# NAVIGATION-PHERIPHERAL.net
KiCad netlist of a schematic drawn in Altium Designer
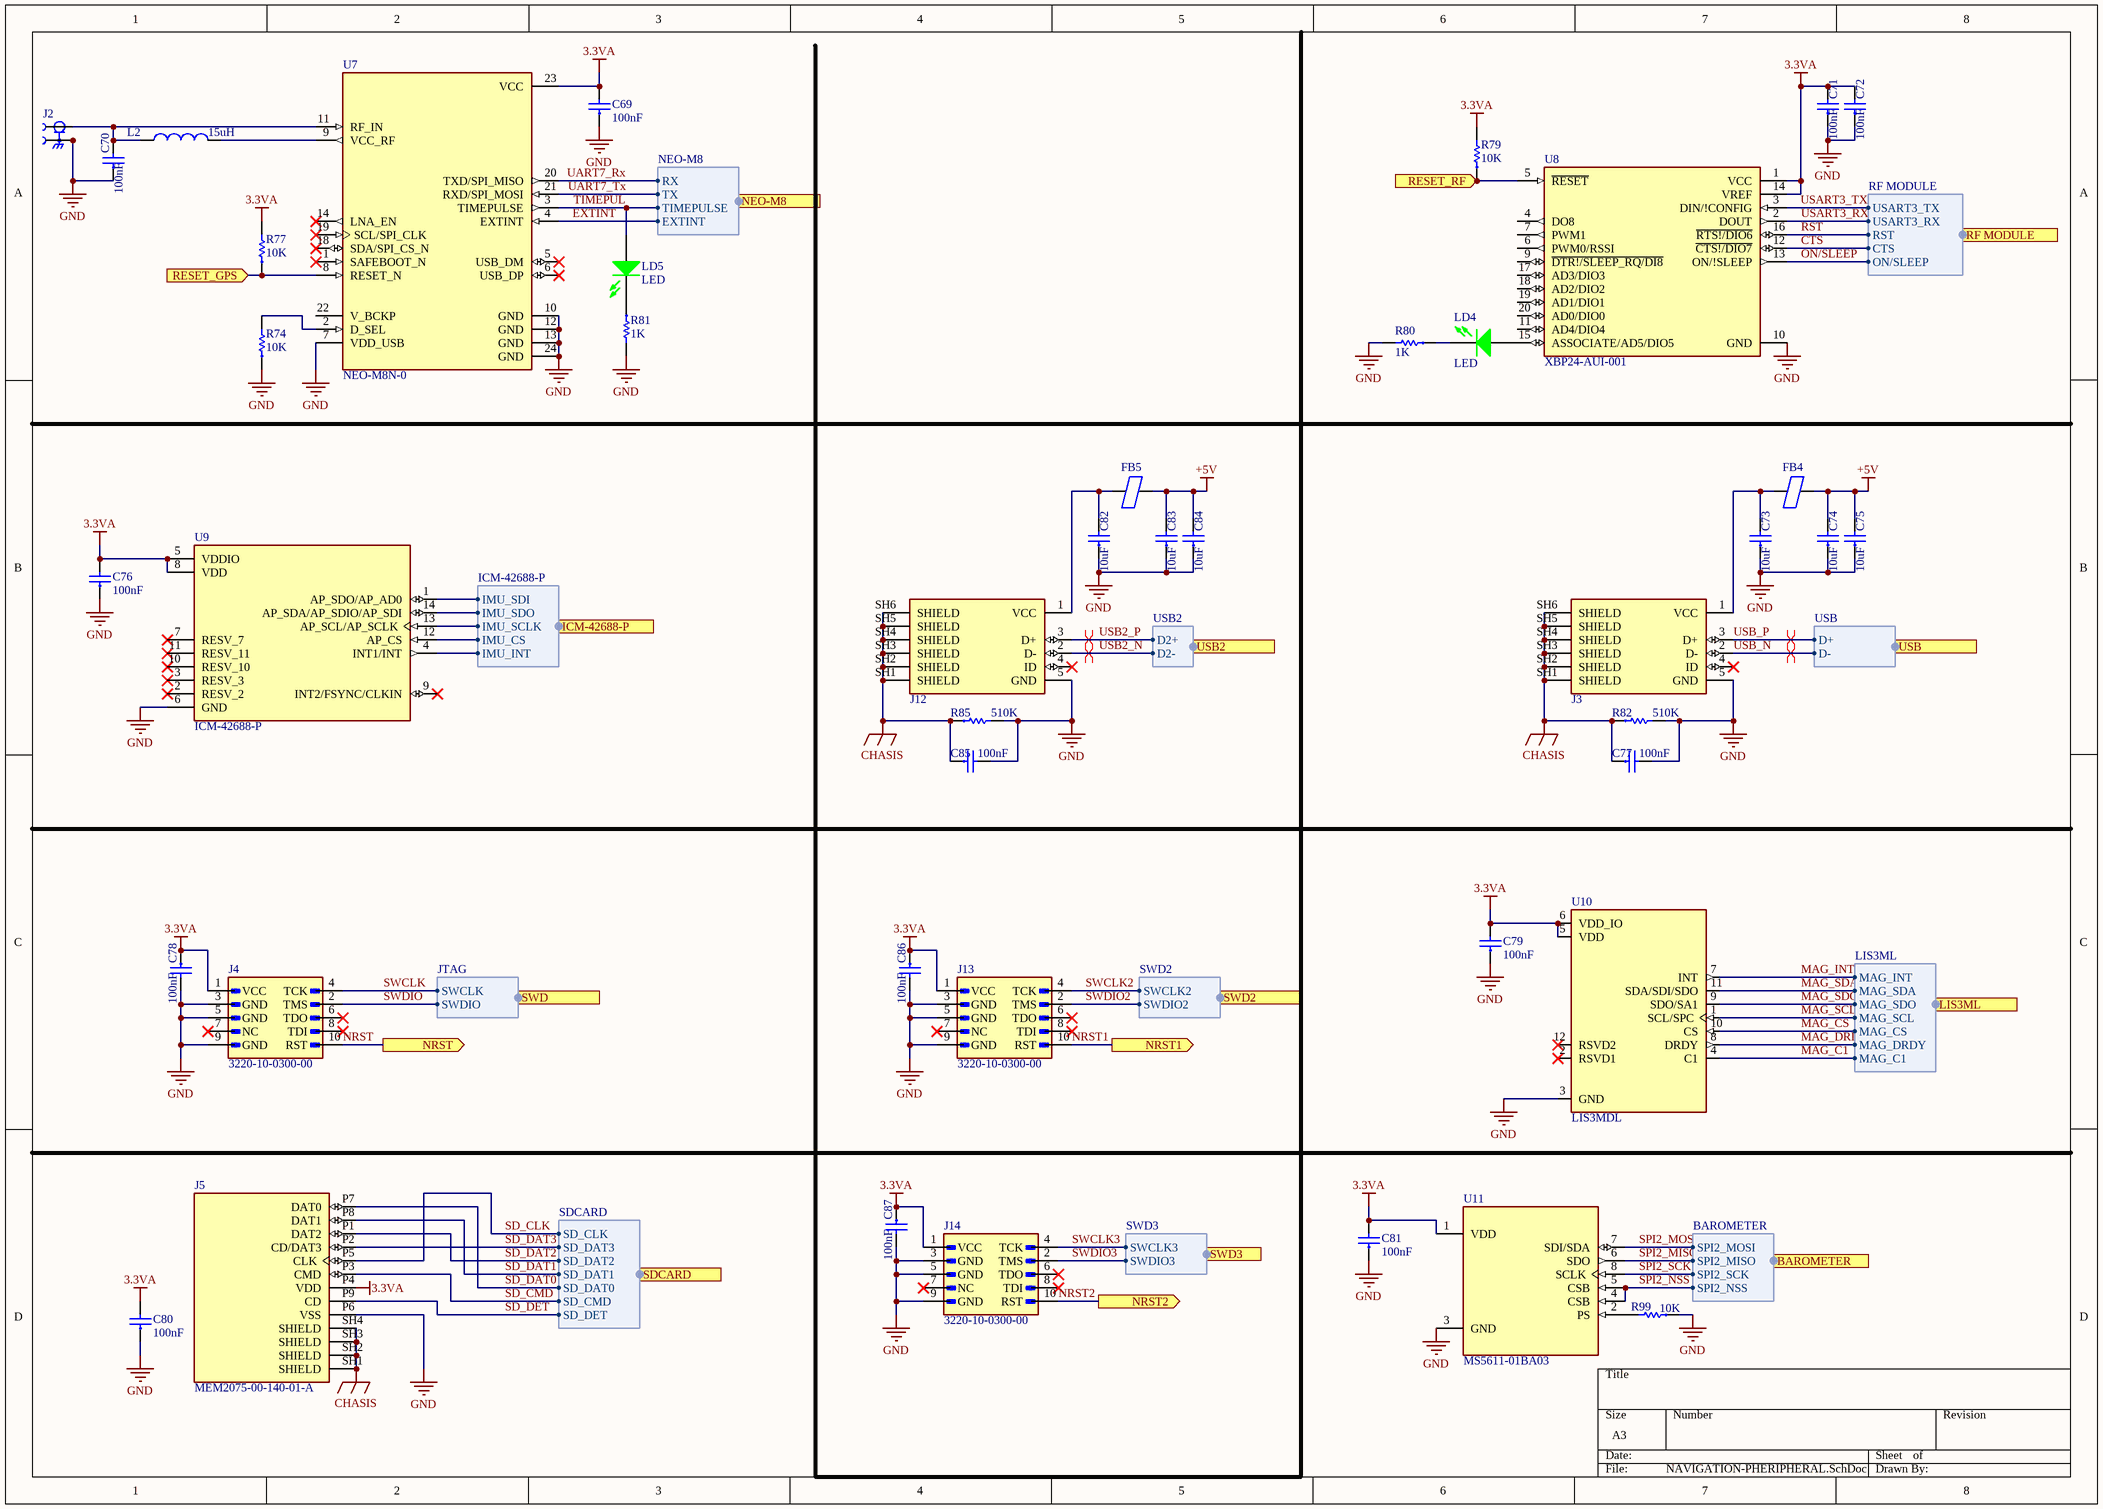
[diagram p0: NAVIGATION-PHERIPHERAL.SchDoc]

(export (version "E")
  (design (tool "Eeschema 10.0.6"))
  (components
    (comp (ref "C69")
      (value "100nF")
      (footprint "CAP-CER0402-0.5H")
      (description "CAP CER 100nF 10% 50V X7R 0402 SMD")
      (libsource (lib "2502-GMQLITE-MAIN") (part "CAPCER0013 100nF 10% 50V X7R 0402 SMD"))
    )
    (comp (ref "C70")
      (value "100nF")
      (footprint "CAP-CER0402-0.5H")
      (description "CAP CER 100nF 10% 50V X7R 0402 SMD")
      (libsource (lib "2502-GMQLITE-MAIN") (part "CAPCER0013 100nF 10% 50V X7R 0402 SMD"))
    )
    (comp (ref "C71")
      (value "100nF")
      (footprint "CAP-CER0402-0.5H")
      (description "CAP CER 100nF 10% 50V X7R 0402 SMD")
      (libsource (lib "2502-GMQLITE-MAIN") (part "CAPCER0013 100nF 10% 50V X7R 0402 SMD"))
    )
    (comp (ref "C72")
      (value "100nF")
      (footprint "CAP-CER0402-0.5H")
      (description "CAP CER 100nF 10% 50V X7R 0402 SMD")
      (libsource (lib "2502-GMQLITE-MAIN") (part "CAPCER0013 100nF 10% 50V X7R 0402 SMD"))
    )
    (comp (ref "C73")
      (value "10uF")
      (footprint "CAP-CER0402-20mil")
      (description "CAP CER 10uF 20% 6.3V X5R 0402 SMD")
      (libsource (lib "2502-GMQLITE-MAIN") (part "CAPCER0040 10uF 20% 6.3V X5R 0402 SMD"))
    )
    (comp (ref "C74")
      (value "10uF")
      (footprint "CAP-CER0402-20mil")
      (description "CAP CER 10uF 20% 6.3V X5R 0402 SMD")
      (libsource (lib "2502-GMQLITE-MAIN") (part "CAPCER0040 10uF 20% 6.3V X5R 0402 SMD"))
    )
    (comp (ref "C75")
      (value "10uF")
      (footprint "CAP-CER0402-20mil")
      (description "CAP CER 10uF 20% 6.3V X5R 0402 SMD")
      (libsource (lib "2502-GMQLITE-MAIN") (part "CAPCER0040 10uF 20% 6.3V X5R 0402 SMD"))
    )
    (comp (ref "C76")
      (value "100nF")
      (footprint "CAP-CER0402-0.5H")
      (description "CAP CER 100nF 10% 50V X7R 0402 SMD")
      (libsource (lib "2502-GMQLITE-MAIN") (part "CAPCER0013 100nF 10% 50V X7R 0402 SMD"))
    )
    (comp (ref "C77")
      (value "100nF")
      (footprint "CAP-CER0603-0.8H")
      (description "CAP CER 100nF 10% 50V X7R 0603 SMD")
      (libsource (lib "2502-GMQLITE-MAIN") (part "CAPCER0001 100nF 10% 50V X7R 0603 SMD"))
    )
    (comp (ref "C78")
      (value "100nF")
      (footprint "CAP-CER0402-0.5H")
      (description "CAP CER 100nF 10% 50V X7R 0402 SMD")
      (libsource (lib "2502-GMQLITE-MAIN") (part "CAPCER0013 100nF 10% 50V X7R 0402 SMD"))
    )
    (comp (ref "C79")
      (value "100nF")
      (footprint "CAP-CER0402-0.5H")
      (description "CAP CER 100nF 10% 50V X7R 0402 SMD")
      (libsource (lib "2502-GMQLITE-MAIN") (part "CAPCER0013 100nF 10% 50V X7R 0402 SMD"))
    )
    (comp (ref "C80")
      (value "100nF")
      (footprint "CAP-CER0402-0.5H")
      (description "CAP CER 100nF 10% 50V X7R 0402 SMD")
      (libsource (lib "2502-GMQLITE-MAIN") (part "CAPCER0013 100nF 10% 50V X7R 0402 SMD"))
    )
    (comp (ref "C81")
      (value "100nF")
      (footprint "CAP-CER0402-0.5H")
      (description "CAP CER 100nF 10% 50V X7R 0402 SMD")
      (libsource (lib "2502-GMQLITE-MAIN") (part "CAPCER0013 100nF 10% 50V X7R 0402 SMD"))
    )
    (comp (ref "C82")
      (value "10uF")
      (footprint "CAP-CER0402-20mil")
      (description "CAP CER 10uF 20% 6.3V X5R 0402 SMD")
      (libsource (lib "2502-GMQLITE-MAIN") (part "CAPCER0040 10uF 20% 6.3V X5R 0402 SMD"))
    )
    (comp (ref "C83")
      (value "10uF")
      (footprint "CAP-CER0402-20mil")
      (description "CAP CER 10uF 20% 6.3V X5R 0402 SMD")
      (libsource (lib "2502-GMQLITE-MAIN") (part "CAPCER0040 10uF 20% 6.3V X5R 0402 SMD"))
    )
    (comp (ref "C84")
      (value "10uF")
      (footprint "CAP-CER0402-20mil")
      (description "CAP CER 10uF 20% 6.3V X5R 0402 SMD")
      (libsource (lib "2502-GMQLITE-MAIN") (part "CAPCER0040 10uF 20% 6.3V X5R 0402 SMD"))
    )
    (comp (ref "C85")
      (value "100nF")
      (footprint "CAP-CER0603-0.8H")
      (description "CAP CER 100nF 10% 50V X7R 0603 SMD")
      (libsource (lib "2502-GMQLITE-MAIN") (part "CAPCER0001 100nF 10% 50V X7R 0603 SMD"))
    )
    (comp (ref "C86")
      (value "100nF")
      (footprint "CAP-CER0402-0.5H")
      (description "CAP CER 100nF 10% 50V X7R 0402 SMD")
      (libsource (lib "2502-GMQLITE-MAIN") (part "CAPCER0013 100nF 10% 50V X7R 0402 SMD"))
    )
    (comp (ref "C87")
      (value "100nF")
      (footprint "CAP-CER0402-0.5H")
      (description "CAP CER 100nF 10% 50V X7R 0402 SMD")
      (libsource (lib "2502-GMQLITE-MAIN") (part "CAPCER0013 100nF 10% 50V X7R 0402 SMD"))
    )
    (comp (ref "FB4")
      (value "100MHz 2A 50mOhm")
      (footprint "FB 0603")
      (description "Ferrite Beads Multi-Layer 120Ohm 25% 100MHz 2A 50mOhm DCR 0603 Paper T/R")
      (fields
        (field (name "MANUFACTURER") "Murata")
        (field (name "MANUFACTURER PART NUMBER") "BLM18PG121SN1D")
      )
      (libsource (lib "POWER_PIN_CAMERA") (part "BLM18PG121SN1D"))
    )
    (comp (ref "FB5")
      (value "100MHz 2A 50mOhm")
      (footprint "FB 0603")
      (description "Ferrite Beads Multi-Layer 120Ohm 25% 100MHz 2A 50mOhm DCR 0603 Paper T/R")
      (fields
        (field (name "MANUFACTURER") "Murata")
        (field (name "MANUFACTURER PART NUMBER") "BLM18PG121SN1D")
      )
      (libsource (lib "POWER_PIN_CAMERA") (part "BLM18PG121SN1D"))
    )
    (comp (ref "J2")
      (value "CONUFL001-SMD")
      (footprint "LINX_CONUFL001-SMD")
      (fields (field (name "MF") "Linx"))
      (libsource (lib "CONUFL001-SMD") (part "CONUFL001-SMD"))
    )
    (comp (ref "J3")
      (value "MICRO B")
      (footprint "MICRO USB B")
      (libsource (lib "BUCKCONVERTER") (part "MICRO USB B"))
    )
    (comp (ref "J4")
      (value "3220-10-0300-00")
      (footprint "CNC_3220-10-0300-00")
      (description "Connector Header Surface Mount 10 position 0.050 (1.27mm)")
      (fields (field (name "MF") "CNC Tech"))
      (libsource (lib "3220-10-0300-00") (part "3220-10-0300-00"))
    )
    (comp (ref "J5")
      (value "MEM2075-00-140-01-A")
      (footprint "GCT_MEM2075-00-140-01-A")
      (description "9 (8 + 1) Position Card Connector microSD Surface Mount, Right Angle Gold")
      (fields (field (name "MF") "Global Connector Technology"))
      (libsource (lib "PIKVM-PI4-0925") (part "MEM2075-00-140-01-A"))
    )
    (comp (ref "J12")
      (value "MICRO B")
      (footprint "MICRO USB B")
      (libsource (lib "BUCKCONVERTER") (part "MICRO USB B"))
    )
    (comp (ref "J13")
      (value "3220-10-0300-00")
      (footprint "CNC_3220-10-0300-00")
      (description "Connector Header Surface Mount 10 position 0.050 (1.27mm)")
      (fields (field (name "MF") "CNC Tech"))
      (libsource (lib "3220-10-0300-00") (part "3220-10-0300-00"))
    )
    (comp (ref "J14")
      (value "3220-10-0300-00")
      (footprint "CNC_3220-10-0300-00")
      (description "Connector Header Surface Mount 10 position 0.050 (1.27mm)")
      (fields (field (name "MF") "CNC Tech"))
      (libsource (lib "3220-10-0300-00") (part "3220-10-0300-00"))
    )
    (comp (ref "L2")
      (value "15uH")
      (footprint "INDC1106X70N")
      (fields
        (field (name "MF") "{'manufacturer': u'Murata Electronics'}")
        (field (name "MP") "LQW15DN100M00D")
      )
      (libsource (lib "LQW15DN100M00D") (part "LQW15DN100M00D"))
    )
    (comp (ref "LD4")
      (value "LED")
      (footprint "LED-IND0402-GRE-0.4H")
      (description "LED IND GRE CLR 2.4V 20mA 0402 SMD")
      (libsource (lib "2502-GMQLITE-MAIN") (part "LEDIND0005 GRE CLR 2.4V 20mA 0402 SMD"))
    )
    (comp (ref "LD5")
      (value "LED")
      (footprint "LED-IND0402-GRE-0.4H")
      (description "LED IND GRE CLR 2.4V 20mA 0402 SMD")
      (libsource (lib "2502-GMQLITE-MAIN") (part "LEDIND0005 GRE CLR 2.4V 20mA 0402 SMD"))
    )
    (comp (ref "R74")
      (value "10K")
      (footprint "RES-CHP0402-0.35H")
      (description "RES CHP 10K 1% 1/16W 0402 SMD")
      (libsource (lib "2502-GMQLITE-MAIN") (part "RESCHP0073 10K 1% 0402 SMD"))
    )
    (comp (ref "R77")
      (value "10K")
      (footprint "RES-CHP0402-0.35H")
      (description "RES CHP 10K 1% 1/16W 0402 SMD")
      (libsource (lib "2502-GMQLITE-MAIN") (part "RESCHP0073 10K 1% 0402 SMD"))
    )
    (comp (ref "R79")
      (value "10K")
      (footprint "RES-CHP0402-0.35H")
      (description "RES CHP 10K 1% 1/16W 0402 SMD")
      (libsource (lib "2502-GMQLITE-MAIN") (part "RESCHP0073 10K 1% 0402 SMD"))
    )
    (comp (ref "R80")
      (value "1K")
      (footprint "RES-CHP0402-0.35H")
      (description "RES CHP 100K 1% 1/16W 0402 SMD")
      (libsource (lib "2502-GMQLITE-MAIN") (part "RESCHP0097 100K 1% 0402 SMD"))
    )
    (comp (ref "R81")
      (value "1K")
      (footprint "RES-CHP0402-0.35H")
      (description "RES CHP 100K 1% 1/16W 0402 SMD")
      (libsource (lib "2502-GMQLITE-MAIN") (part "RESCHP0097 100K 1% 0402 SMD"))
    )
    (comp (ref "R82")
      (value "510K")
      (footprint "RES-CHP0402-0.35H")
      (description "RES CHP 510K 1% 1/16W 0402 SMD")
      (libsource (lib "2502-GMQLITE-MAIN") (part "RESCHP0114 510K 1% 0402 SMD"))
    )
    (comp (ref "R85")
      (value "510K")
      (footprint "RES-CHP0402-0.35H")
      (description "RES CHP 510K 1% 1/16W 0402 SMD")
      (libsource (lib "2502-GMQLITE-MAIN") (part "RESCHP0114 510K 1% 0402 SMD"))
    )
    (comp (ref "R99")
      (value "10K")
      (footprint "RES-CHP0402-0.35H")
      (description "RES CHP 100K 1% 1/16W 0402 SMD")
      (libsource (lib "2502-GMQLITE-MAIN") (part "RESCHP0097 100K 1% 0402 SMD"))
    )
    (comp (ref "U7")
      (value "NEO-M8N-0")
      (footprint "XCVR_NEO-M8N-0")
      (description "series RF Receiver BeiDou, Galileo, GLONASS, GNSS, GPS 1.575GHz -167dBm - - -")
      (fields (field (name "MF") "U-Blox America"))
      (libsource (lib "NEO-M8N-0") (part "NEO-M8N-0"))
    )
    (comp (ref "U8")
      (value "XBP24-AUI-001")
      (footprint "XBP24-AUI-001")
      (description "Xbee-Pro 802.15.4, 63mw, Wire Antenna, 250000 Bps; Higher Tran")
      (libsource (lib "XBP24-AUI-001") (part "XBP24-AUI-001"))
    )
    (comp (ref "U9")
      (value "ICM-42688-P")
      (footprint "PQFN50P300X250X97-14N")
      (description "Accelerometer, Gyroscope, 6 Axis Sensor Output")
      (libsource (lib "ICM-42688-P") (part "ICM-42688-P"))
    )
    (comp (ref "U10")
      (value "LIS3MDL")
      (footprint "XDCR_LIS3MDL")
      (description "Magnetoresistive Sensor X, Y, Z Axis 12-LGA (2x2)")
      (fields (field (name "MF") "STMicroelectronics"))
      (libsource (lib "LIS3MDL") (part "LIS3MDL"))
    )
    (comp (ref "U11")
      (value "MS5611-01BA03")
      (footprint "SON125P500X300X100-8N")
      (description "Pressure Sensor 0.15PSI ~ 17.4PSI (1kPa ~ 120kPa) Absolute - 24 b 8-SMD")
      (fields (field (name "MF") "TE Connectivity"))
      (libsource (lib "MS5611-01BA03") (part "MS5611-01BA03"))
    )
  )
  (nets
    (net (code "13") (name "+5V") (class "Default")
      (node (ref "C74") (pin "2") (pinfunction "2_2") (pintype "passive"))
      (node (ref "C75") (pin "2") (pinfunction "2_2") (pintype "passive"))
      (node (ref "C83") (pin "2") (pinfunction "2_2") (pintype "passive"))
      (node (ref "C84") (pin "2") (pinfunction "2_2") (pintype "passive"))
      (node (ref "FB4") (pin "2") (pinfunction "2_2") (pintype "passive"))
      (node (ref "FB5") (pin "2") (pinfunction "2_2") (pintype "passive"))
    )
    (net (code "14") (name "/CTS") (class "Default")
      (node (ref "U8") (pin "12") (pinfunction "~{CTS!/DIO7}_12") (pintype "bidirectional"))
    )
    (net (code "15") (name "/EXTINT") (class "Default")
      (node (ref "U7") (pin "4") (pinfunction "EXTINT_4") (pintype "input"))
    )
    (net (code "16") (name "/IMU_CS") (class "Default")
      (node (ref "U9") (pin "12") (pinfunction "AP_CS_12") (pintype "input"))
    )
    (net (code "17") (name "/IMU_INT") (class "Default")
      (node (ref "U9") (pin "4") (pinfunction "INT1/INT_4") (pintype "output"))
    )
    (net (code "18") (name "/IMU_SCLK") (class "Default")
      (node (ref "U9") (pin "13") (pinfunction "AP_SCL/AP_SCLK_13") (pintype "input"))
    )
    (net (code "19") (name "/IMU_SDI") (class "Default")
      (node (ref "U9") (pin "1") (pinfunction "AP_SDO/AP_AD0_1") (pintype "bidirectional"))
    )
    (net (code "20") (name "/IMU_SDO") (class "Default")
      (node (ref "U9") (pin "14") (pinfunction "AP_SDA/AP_SDIO/AP_SDI_14") (pintype "bidirectional"))
    )
    (net (code "21") (name "/MAG_C1") (class "Default")
      (node (ref "U10") (pin "4") (pinfunction "C1_4") (pintype "passive"))
    )
    (net (code "22") (name "/MAG_CS") (class "Default")
      (node (ref "U10") (pin "10") (pinfunction "CS_10") (pintype "input"))
    )
    (net (code "23") (name "/MAG_DRDY") (class "Default")
      (node (ref "U10") (pin "8") (pinfunction "DRDY_8") (pintype "output"))
    )
    (net (code "24") (name "/MAG_INT") (class "Default")
      (node (ref "U10") (pin "7") (pinfunction "INT_7") (pintype "output"))
    )
    (net (code "25") (name "/MAG_SCL") (class "Default")
      (node (ref "U10") (pin "1") (pinfunction "SCL/SPC_1") (pintype "input"))
    )
    (net (code "26") (name "/MAG_SDA") (class "Default")
      (node (ref "U10") (pin "11") (pinfunction "SDA/SDI/SDO_11") (pintype "bidirectional"))
    )
    (net (code "27") (name "/MAG_SDO") (class "Default")
      (node (ref "U10") (pin "9") (pinfunction "SDO/SA1_9") (pintype "bidirectional"))
    )
    (net (code "28") (name "/NRST") (class "Default")
      (node (ref "J4") (pin "10") (pinfunction "RST_10") (pintype "passive"))
    )
    (net (code "29") (name "/NRST1") (class "Default")
      (node (ref "J13") (pin "10") (pinfunction "RST_10") (pintype "passive"))
    )
    (net (code "30") (name "/NRST2") (class "Default")
      (node (ref "J14") (pin "10") (pinfunction "RST_10") (pintype "passive"))
    )
    (net (code "31") (name "/ON{slash}SLEEP") (class "Default")
      (node (ref "U8") (pin "13") (pinfunction "ON/!SLEEP_13") (pintype "output"))
    )
    (net (code "32") (name "/RESET_GPS") (class "Default")
      (node (ref "R77") (pin "1") (pinfunction "1_1") (pintype "passive"))
      (node (ref "U7") (pin "8") (pinfunction "RESET_N_8") (pintype "input"))
    )
    (net (code "33") (name "/RESET_RF") (class "Default")
      (node (ref "R79") (pin "1") (pinfunction "1_1") (pintype "passive"))
      (node (ref "U8") (pin "5") (pinfunction "~{RESET}_5") (pintype "input"))
    )
    (net (code "34") (name "/RST") (class "Default")
      (node (ref "U8") (pin "16") (pinfunction "~{RTS!/DIO6}_16") (pintype "bidirectional"))
    )
    (net (code "35") (name "/SD_CLK") (class "Default")
      (node (ref "J5") (pin "P5") (pinfunction "CLK_P5") (pintype "bidirectional"))
    )
    (net (code "36") (name "/SD_CMD") (class "Default")
      (node (ref "J5") (pin "P3") (pinfunction "CMD_P3") (pintype "bidirectional"))
    )
    (net (code "37") (name "/SD_DAT0") (class "Default")
      (node (ref "J5") (pin "P7") (pinfunction "DAT0_P7") (pintype "bidirectional"))
    )
    (net (code "38") (name "/SD_DAT1") (class "Default")
      (node (ref "J5") (pin "P8") (pinfunction "DAT1_P8") (pintype "bidirectional"))
    )
    (net (code "39") (name "/SD_DAT2") (class "Default")
      (node (ref "J5") (pin "P1") (pinfunction "DAT2_P1") (pintype "bidirectional"))
    )
    (net (code "40") (name "/SD_DAT3") (class "Default")
      (node (ref "J5") (pin "P2") (pinfunction "CD/DAT3_P2") (pintype "bidirectional"))
    )
    (net (code "41") (name "/SD_DET") (class "Default")
      (node (ref "J5") (pin "P9") (pinfunction "CD_P9") (pintype "passive"))
    )
    (net (code "42") (name "/SPI2_MISO") (class "Default")
      (node (ref "U11") (pin "6") (pinfunction "SDO_6") (pintype "output"))
    )
    (net (code "43") (name "/SPI2_MOSI") (class "Default")
      (node (ref "U11") (pin "7") (pinfunction "SDI/SDA_7") (pintype "bidirectional"))
    )
    (net (code "44") (name "/SPI2_NSS") (class "Default")
      (node (ref "U11") (pin "4") (pinfunction "CSB_4") (pintype "input"))
      (node (ref "U11") (pin "5") (pinfunction "CSB_5") (pintype "input"))
    )
    (net (code "45") (name "/SPI2_SCK") (class "Default")
      (node (ref "U11") (pin "8") (pinfunction "SCLK_8") (pintype "input"))
    )
    (net (code "46") (name "/SWCLK") (class "Default")
      (node (ref "J4") (pin "4") (pinfunction "TCK_4") (pintype "passive"))
    )
    (net (code "47") (name "/SWCLK2") (class "Default")
      (node (ref "J13") (pin "4") (pinfunction "TCK_4") (pintype "passive"))
    )
    (net (code "48") (name "/SWCLK3") (class "Default")
      (node (ref "J14") (pin "4") (pinfunction "TCK_4") (pintype "passive"))
    )
    (net (code "49") (name "/SWDIO") (class "Default")
      (node (ref "J4") (pin "2") (pinfunction "TMS_2") (pintype "passive"))
    )
    (net (code "50") (name "/SWDIO2") (class "Default")
      (node (ref "J13") (pin "2") (pinfunction "TMS_2") (pintype "passive"))
    )
    (net (code "51") (name "/SWDIO3") (class "Default")
      (node (ref "J14") (pin "2") (pinfunction "TMS_2") (pintype "passive"))
    )
    (net (code "52") (name "/TIMEPUL") (class "Default")
      (node (ref "LD5") (pin "1") (pinfunction "A_1") (pintype "passive"))
      (node (ref "U7") (pin "3") (pinfunction "TIMEPULSE_3") (pintype "output"))
    )
    (net (code "53") (name "/UART7_Rx") (class "Default")
      (node (ref "U7") (pin "20") (pinfunction "TXD/SPI_MISO_20") (pintype "output"))
    )
    (net (code "54") (name "/UART7_Tx") (class "Default")
      (node (ref "U7") (pin "21") (pinfunction "RXD/SPI_MOSI_21") (pintype "input"))
    )
    (net (code "55") (name "/USART3_RX") (class "Default")
      (node (ref "U8") (pin "2") (pinfunction "DOUT_2") (pintype "output"))
    )
    (net (code "56") (name "/USART3_TX") (class "Default")
      (node (ref "U8") (pin "3") (pinfunction "DIN/!CONFIG_3") (pintype "input"))
    )
    (net (code "57") (name "/USB2_N") (class "Default")
      (node (ref "J12") (pin "2") (pinfunction "D-_2") (pintype "bidirectional"))
    )
    (net (code "58") (name "/USB2_P") (class "Default")
      (node (ref "J12") (pin "3") (pinfunction "D+_3") (pintype "bidirectional"))
    )
    (net (code "59") (name "/USB_N") (class "Default")
      (node (ref "J3") (pin "2") (pinfunction "D-_2") (pintype "bidirectional"))
    )
    (net (code "60") (name "/USB_P") (class "Default")
      (node (ref "J3") (pin "3") (pinfunction "D+_3") (pintype "bidirectional"))
    )
    (net (code "72") (name "3.3VA") (class "Default")
      (node (ref "C69") (pin "2") (pinfunction "2_2") (pintype "passive"))
      (node (ref "C71") (pin "2") (pinfunction "2_2") (pintype "passive"))
      (node (ref "C72") (pin "2") (pinfunction "2_2") (pintype "passive"))
      (node (ref "C76") (pin "2") (pinfunction "2_2") (pintype "passive"))
      (node (ref "C78") (pin "1") (pinfunction "1_1") (pintype "passive"))
      (node (ref "C79") (pin "2") (pinfunction "2_2") (pintype "passive"))
      (node (ref "C80") (pin "2") (pinfunction "2_2") (pintype "passive"))
      (node (ref "C81") (pin "2") (pinfunction "2_2") (pintype "passive"))
      (node (ref "C86") (pin "1") (pinfunction "1_1") (pintype "passive"))
      (node (ref "C87") (pin "1") (pinfunction "1_1") (pintype "passive"))
      (node (ref "J13") (pin "1") (pinfunction "VCC_1") (pintype "passive"))
      (node (ref "J14") (pin "1") (pinfunction "VCC_1") (pintype "passive"))
      (node (ref "J4") (pin "1") (pinfunction "VCC_1") (pintype "passive"))
      (node (ref "J5") (pin "P4") (pinfunction "VDD_P4") (pintype "power_in"))
      (node (ref "R77") (pin "2") (pinfunction "2_2") (pintype "passive"))
      (node (ref "R79") (pin "2") (pinfunction "2_2") (pintype "passive"))
      (node (ref "U10") (pin "5") (pinfunction "VDD_5") (pintype "power_in"))
      (node (ref "U10") (pin "6") (pinfunction "VDD_IO_6") (pintype "power_in"))
      (node (ref "U11") (pin "1") (pinfunction "VDD_1") (pintype "power_in"))
      (node (ref "U7") (pin "23") (pinfunction "VCC_23") (pintype "power_in"))
      (node (ref "U8") (pin "1") (pinfunction "VCC_1") (pintype "power_in"))
      (node (ref "U8") (pin "14") (pinfunction "VREF_14") (pintype "power_in"))
      (node (ref "U9") (pin "5") (pinfunction "VDDIO_5") (pintype "power_in"))
      (node (ref "U9") (pin "8") (pinfunction "VDD_8") (pintype "power_in"))
    )
    (net (code "73") (name "CHASIS") (class "Default")
      (node (ref "C77") (pin "1") (pinfunction "1_1") (pintype "passive"))
      (node (ref "C85") (pin "1") (pinfunction "1_1") (pintype "passive"))
      (node (ref "J12") (pin "SH1") (pinfunction "SHIELD_SH1") (pintype "passive"))
      (node (ref "J12") (pin "SH2") (pinfunction "SHIELD_SH2") (pintype "passive"))
      (node (ref "J12") (pin "SH3") (pinfunction "SHIELD_SH3") (pintype "passive"))
      (node (ref "J12") (pin "SH4") (pinfunction "SHIELD_SH4") (pintype "passive"))
      (node (ref "J12") (pin "SH5") (pinfunction "SHIELD_SH5") (pintype "passive"))
      (node (ref "J12") (pin "SH6") (pinfunction "SHIELD_SH6") (pintype "passive"))
      (node (ref "J3") (pin "SH1") (pinfunction "SHIELD_SH1") (pintype "passive"))
      (node (ref "J3") (pin "SH2") (pinfunction "SHIELD_SH2") (pintype "passive"))
      (node (ref "J3") (pin "SH3") (pinfunction "SHIELD_SH3") (pintype "passive"))
      (node (ref "J3") (pin "SH4") (pinfunction "SHIELD_SH4") (pintype "passive"))
      (node (ref "J3") (pin "SH5") (pinfunction "SHIELD_SH5") (pintype "passive"))
      (node (ref "J3") (pin "SH6") (pinfunction "SHIELD_SH6") (pintype "passive"))
      (node (ref "J5") (pin "SH1") (pinfunction "SHIELD_SH1") (pintype "power_in"))
      (node (ref "J5") (pin "SH2") (pinfunction "SHIELD_SH2") (pintype "power_in"))
      (node (ref "J5") (pin "SH3") (pinfunction "SHIELD_SH3") (pintype "power_in"))
      (node (ref "J5") (pin "SH4") (pinfunction "SHIELD_SH4") (pintype "power_in"))
      (node (ref "R82") (pin "1") (pinfunction "1_1") (pintype "passive"))
      (node (ref "R85") (pin "1") (pinfunction "1_1") (pintype "passive"))
    )
    (net (code "74") (name "GND") (class "Default")
      (node (ref "C69") (pin "1") (pinfunction "1_1") (pintype "passive"))
      (node (ref "C70") (pin "1") (pinfunction "1_1") (pintype "passive"))
      (node (ref "C71") (pin "1") (pinfunction "1_1") (pintype "passive"))
      (node (ref "C72") (pin "1") (pinfunction "1_1") (pintype "passive"))
      (node (ref "C73") (pin "1") (pinfunction "1_1") (pintype "passive"))
      (node (ref "C74") (pin "1") (pinfunction "1_1") (pintype "passive"))
      (node (ref "C75") (pin "1") (pinfunction "1_1") (pintype "passive"))
      (node (ref "C76") (pin "1") (pinfunction "1_1") (pintype "passive"))
      (node (ref "C77") (pin "2") (pinfunction "2_2") (pintype "passive"))
      (node (ref "C78") (pin "2") (pinfunction "2_2") (pintype "passive"))
      (node (ref "C79") (pin "1") (pinfunction "1_1") (pintype "passive"))
      (node (ref "C80") (pin "1") (pinfunction "1_1") (pintype "passive"))
      (node (ref "C81") (pin "1") (pinfunction "1_1") (pintype "passive"))
      (node (ref "C82") (pin "1") (pinfunction "1_1") (pintype "passive"))
      (node (ref "C83") (pin "1") (pinfunction "1_1") (pintype "passive"))
      (node (ref "C84") (pin "1") (pinfunction "1_1") (pintype "passive"))
      (node (ref "C85") (pin "2") (pinfunction "2_2") (pintype "passive"))
      (node (ref "C86") (pin "2") (pinfunction "2_2") (pintype "passive"))
      (node (ref "C87") (pin "2") (pinfunction "2_2") (pintype "passive"))
      (node (ref "J12") (pin "5") (pinfunction "GND_5") (pintype "power_in"))
      (node (ref "J13") (pin "3") (pinfunction "GND_3") (pintype "passive"))
      (node (ref "J13") (pin "5") (pinfunction "GND_5") (pintype "passive"))
      (node (ref "J13") (pin "9") (pinfunction "GND_9") (pintype "passive"))
      (node (ref "J14") (pin "3") (pinfunction "GND_3") (pintype "passive"))
      (node (ref "J14") (pin "5") (pinfunction "GND_5") (pintype "passive"))
      (node (ref "J14") (pin "9") (pinfunction "GND_9") (pintype "passive"))
      (node (ref "J2") (pin "2") (pinfunction "2_2") (pintype "passive"))
      (node (ref "J2") (pin "3") (pinfunction "2_3") (pintype "passive"))
      (node (ref "J3") (pin "5") (pinfunction "GND_5") (pintype "power_in"))
      (node (ref "J4") (pin "3") (pinfunction "GND_3") (pintype "passive"))
      (node (ref "J4") (pin "5") (pinfunction "GND_5") (pintype "passive"))
      (node (ref "J4") (pin "9") (pinfunction "GND_9") (pintype "passive"))
      (node (ref "J5") (pin "P6") (pinfunction "VSS_P6") (pintype "power_in"))
      (node (ref "R74") (pin "1") (pinfunction "1_1") (pintype "passive"))
      (node (ref "R80") (pin "2") (pinfunction "2_2") (pintype "passive"))
      (node (ref "R81") (pin "2") (pinfunction "2_2") (pintype "passive"))
      (node (ref "R82") (pin "2") (pinfunction "2_2") (pintype "passive"))
      (node (ref "R85") (pin "2") (pinfunction "2_2") (pintype "passive"))
      (node (ref "R99") (pin "1") (pinfunction "1_1") (pintype "passive"))
      (node (ref "U10") (pin "3") (pinfunction "GND_3") (pintype "power_in"))
      (node (ref "U11") (pin "3") (pinfunction "GND_3") (pintype "power_in"))
      (node (ref "U7") (pin "10") (pinfunction "GND_10") (pintype "power_in"))
      (node (ref "U7") (pin "12") (pinfunction "GND_12") (pintype "power_in"))
      (node (ref "U7") (pin "13") (pinfunction "GND_13") (pintype "power_in"))
      (node (ref "U7") (pin "24") (pinfunction "GND_24") (pintype "power_in"))
      (node (ref "U7") (pin "7") (pinfunction "VDD_USB_7") (pintype "power_in"))
      (node (ref "U8") (pin "10") (pinfunction "GND_10") (pintype "power_in"))
      (node (ref "U9") (pin "6") (pinfunction "GND_6") (pintype "power_in"))
    )
    (net (code "75") (name "Net-(J3-VCC)") (class "Default")
      (node (ref "C73") (pin "2") (pinfunction "2_2") (pintype "passive"))
      (node (ref "FB4") (pin "1") (pinfunction "1_1") (pintype "passive"))
      (node (ref "J3") (pin "1") (pinfunction "VCC_1") (pintype "power_in"))
    )
    (net (code "76") (name "Net-(J12-VCC)") (class "Default")
      (node (ref "C82") (pin "2") (pinfunction "2_2") (pintype "passive"))
      (node (ref "FB5") (pin "1") (pinfunction "1_1") (pintype "passive"))
      (node (ref "J12") (pin "1") (pinfunction "VCC_1") (pintype "power_in"))
    )
    (net (code "77") (name "Net-(LD4-A)") (class "Default")
      (node (ref "LD4") (pin "1") (pinfunction "A_1") (pintype "passive"))
      (node (ref "U8") (pin "15") (pinfunction "ASSOCIATE/AD5/DIO5_15") (pintype "bidirectional"))
    )
    (net (code "78") (name "Net-(LD4-K)") (class "Default")
      (node (ref "LD4") (pin "2") (pinfunction "K_2") (pintype "passive"))
      (node (ref "R80") (pin "1") (pinfunction "1_1") (pintype "passive"))
    )
    (net (code "79") (name "Net-(LD5-K)") (class "Default")
      (node (ref "LD5") (pin "2") (pinfunction "K_2") (pintype "passive"))
      (node (ref "R81") (pin "1") (pinfunction "1_1") (pintype "passive"))
    )
    (net (code "80") (name "Net-(U7-D_SEL)") (class "Default")
      (node (ref "R74") (pin "2") (pinfunction "2_2") (pintype "passive"))
      (node (ref "U7") (pin "2") (pinfunction "D_SEL_2") (pintype "input"))
    )
    (net (code "81") (name "Net-(U7-RF_IN)") (class "Default")
      (node (ref "C70") (pin "2") (pinfunction "2_2") (pintype "passive"))
      (node (ref "J2") (pin "1") (pinfunction "1_1") (pintype "passive"))
      (node (ref "L2") (pin "1") (pinfunction "1_1") (pintype "passive"))
      (node (ref "U7") (pin "11") (pinfunction "RF_IN_11") (pintype "input"))
    )
    (net (code "82") (name "Net-(U7-VCC_RF)") (class "Default")
      (node (ref "L2") (pin "2") (pinfunction "2_2") (pintype "passive"))
      (node (ref "U7") (pin "9") (pinfunction "VCC_RF_9") (pintype "output"))
    )
    (net (code "83") (name "Net-(U11-PS)") (class "Default")
      (node (ref "R99") (pin "2") (pinfunction "2_2") (pintype "passive"))
      (node (ref "U11") (pin "2") (pinfunction "PS_2") (pintype "input"))
    )
    (net (code "84") (name "unconnected-(J3-ID-Pad4)") (class "Default")
      (node (ref "J3") (pin "4") (pinfunction "ID_4") (pintype "bidirectional+no_connect"))
    )
    (net (code "85") (name "unconnected-(J4-NC-Pad7)") (class "Default")
      (node (ref "J4") (pin "7") (pinfunction "NC_7") (pintype "passive+no_connect"))
    )
    (net (code "86") (name "unconnected-(J4-TDI-Pad8)") (class "Default")
      (node (ref "J4") (pin "8") (pinfunction "TDI_8") (pintype "passive+no_connect"))
    )
    (net (code "87") (name "unconnected-(J4-TDO-Pad6)") (class "Default")
      (node (ref "J4") (pin "6") (pinfunction "TDO_6") (pintype "passive+no_connect"))
    )
    (net (code "88") (name "unconnected-(J12-ID-Pad4)") (class "Default")
      (node (ref "J12") (pin "4") (pinfunction "ID_4") (pintype "bidirectional+no_connect"))
    )
    (net (code "89") (name "unconnected-(J13-NC-Pad7)") (class "Default")
      (node (ref "J13") (pin "7") (pinfunction "NC_7") (pintype "passive+no_connect"))
    )
    (net (code "90") (name "unconnected-(J13-TDI-Pad8)") (class "Default")
      (node (ref "J13") (pin "8") (pinfunction "TDI_8") (pintype "passive+no_connect"))
    )
    (net (code "91") (name "unconnected-(J13-TDO-Pad6)") (class "Default")
      (node (ref "J13") (pin "6") (pinfunction "TDO_6") (pintype "passive+no_connect"))
    )
    (net (code "92") (name "unconnected-(J14-NC-Pad7)") (class "Default")
      (node (ref "J14") (pin "7") (pinfunction "NC_7") (pintype "passive+no_connect"))
    )
    (net (code "93") (name "unconnected-(J14-TDI-Pad8)") (class "Default")
      (node (ref "J14") (pin "8") (pinfunction "TDI_8") (pintype "passive+no_connect"))
    )
    (net (code "94") (name "unconnected-(J14-TDO-Pad6)") (class "Default")
      (node (ref "J14") (pin "6") (pinfunction "TDO_6") (pintype "passive+no_connect"))
    )
    (net (code "95") (name "unconnected-(U7-LNA_EN-Pad14)") (class "Default")
      (node (ref "U7") (pin "14") (pinfunction "LNA_EN_14") (pintype "output+no_connect"))
    )
    (net (code "96") (name "unconnected-(U7-SAFEBOOT_N-Pad1)") (class "Default")
      (node (ref "U7") (pin "1") (pinfunction "SAFEBOOT_N_1") (pintype "input+no_connect"))
    )
    (net (code "97") (name "unconnected-(U7-SCL{slash}SPI_CLK-Pad19)") (class "Default")
      (node (ref "U7") (pin "19") (pinfunction "SCL/SPI_CLK_19") (pintype "input+no_connect"))
    )
    (net (code "98") (name "unconnected-(U7-SDA{slash}SPI_CS_N-Pad18)") (class "Default")
      (node (ref "U7") (pin "18") (pinfunction "SDA/SPI_CS_N_18") (pintype "bidirectional+no_connect"))
    )
    (net (code "99") (name "unconnected-(U7-USB_DM-Pad5)") (class "Default")
      (node (ref "U7") (pin "5") (pinfunction "USB_DM_5") (pintype "bidirectional+no_connect"))
    )
    (net (code "100") (name "unconnected-(U7-USB_DP-Pad6)") (class "Default")
      (node (ref "U7") (pin "6") (pinfunction "USB_DP_6") (pintype "bidirectional+no_connect"))
    )
    (net (code "101") (name "unconnected-(U7-V_BCKP-Pad22)") (class "Default")
      (node (ref "U7") (pin "22") (pinfunction "V_BCKP_22") (pintype "power_in"))
    )
    (net (code "102") (name "unconnected-(U8-AD0{slash}DIO0-Pad20)") (class "Default")
      (node (ref "U8") (pin "20") (pinfunction "AD0/DIO0_20") (pintype "bidirectional"))
    )
    (net (code "103") (name "unconnected-(U8-AD1{slash}DIO1-Pad19)") (class "Default")
      (node (ref "U8") (pin "19") (pinfunction "AD1/DIO1_19") (pintype "bidirectional"))
    )
    (net (code "104") (name "unconnected-(U8-AD2{slash}DIO2-Pad18)") (class "Default")
      (node (ref "U8") (pin "18") (pinfunction "AD2/DIO2_18") (pintype "bidirectional"))
    )
    (net (code "105") (name "unconnected-(U8-AD3{slash}DIO3-Pad17)") (class "Default")
      (node (ref "U8") (pin "17") (pinfunction "AD3/DIO3_17") (pintype "bidirectional"))
    )
    (net (code "106") (name "unconnected-(U8-AD4{slash}DIO4-Pad11)") (class "Default")
      (node (ref "U8") (pin "11") (pinfunction "AD4/DIO4_11") (pintype "bidirectional"))
    )
    (net (code "107") (name "unconnected-(U8-DO8-Pad4)") (class "Default")
      (node (ref "U8") (pin "4") (pinfunction "DO8_4") (pintype "output"))
    )
    (net (code "108") (name "unconnected-(U8-PWM0{slash}RSSI-Pad6)") (class "Default")
      (node (ref "U8") (pin "6") (pinfunction "PWM0/RSSI_6") (pintype "output"))
    )
    (net (code "109") (name "unconnected-(U8-PWM1-Pad7)") (class "Default")
      (node (ref "U8") (pin "7") (pinfunction "PWM1_7") (pintype "output"))
    )
    (net (code "110") (name "unconnected-(U8-~{DTR!{slash}SLEEP_RQ{slash}DI8}-Pad9)") (class "Default")
      (node (ref "U8") (pin "9") (pinfunction "~{DTR!/SLEEP_RQ/DI8}_9") (pintype "bidirectional"))
    )
    (net (code "111") (name "unconnected-(U9-INT2{slash}FSYNC{slash}CLKIN-Pad9)") (class "Default")
      (node (ref "U9") (pin "9") (pinfunction "INT2/FSYNC/CLKIN_9") (pintype "bidirectional+no_connect"))
    )
    (net (code "112") (name "unconnected-(U9-RESV_2-Pad2)") (class "Default")
      (node (ref "U9") (pin "2") (pinfunction "RESV_2_2") (pintype "passive+no_connect"))
    )
    (net (code "113") (name "unconnected-(U9-RESV_3-Pad3)") (class "Default")
      (node (ref "U9") (pin "3") (pinfunction "RESV_3_3") (pintype "passive+no_connect"))
    )
    (net (code "114") (name "unconnected-(U9-RESV_7-Pad7)") (class "Default")
      (node (ref "U9") (pin "7") (pinfunction "RESV_7_7") (pintype "passive+no_connect"))
    )
    (net (code "115") (name "unconnected-(U9-RESV_10-Pad10)") (class "Default")
      (node (ref "U9") (pin "10") (pinfunction "RESV_10_10") (pintype "passive+no_connect"))
    )
    (net (code "116") (name "unconnected-(U9-RESV_11-Pad11)") (class "Default")
      (node (ref "U9") (pin "11") (pinfunction "RESV_11_11") (pintype "passive+no_connect"))
    )
    (net (code "117") (name "unconnected-(U10-RSVD1-Pad2)") (class "Default")
      (node (ref "U10") (pin "2") (pinfunction "RSVD1_2") (pintype "passive+no_connect"))
    )
    (net (code "118") (name "unconnected-(U10-RSVD2-Pad12)") (class "Default")
      (node (ref "U10") (pin "12") (pinfunction "RSVD2_12") (pintype "passive+no_connect"))
    )
  )
)
